# DB_Capacitance-X02.net
KiCad netlist of a schematic drawn in Altium Designer
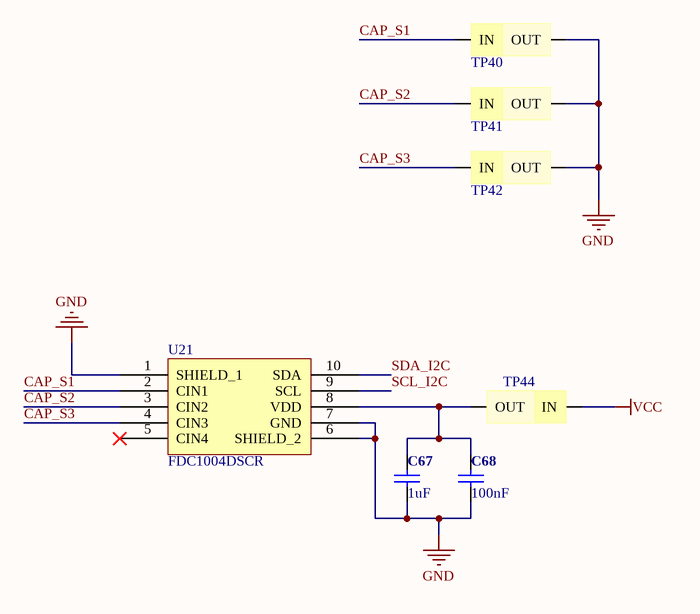
[diagram p0: DB_Capacitance-X02.SchDoc]

(export (version "E")
  (design (tool "Eeschema 10.0.6"))
  (components
    (comp (ref "C67")
      (value "1uF")
      (footprint "C0402")
      (fields
        (field (name "MANUFACTURER") "Yageo")
        (field (name "MANUFACTURER PART NUMBER") "CC0402MRX5R5BB105")
        (field (name "TOLERANCE") "20%")
      )
      (libsource (lib "DB-X02") (part "C-0402(1005)"))
    )
    (comp (ref "C68")
      (value "100nF")
      (footprint "C0402")
      (fields
        (field (name "MANUFACTURER") "Taiyo Yuden")
        (field (name "MANUFACTURER PART NUMBER") "TMK105BJ104KV-F")
        (field (name "TOLERANCE") "10%")
      )
      (libsource (lib "DB-X02") (part "C-0402(1005)"))
    )
    (comp (ref "TP40")
      (value "JUMPER")
      (footprint "JUMPER")
      (description "SHUNT LP W/HANDLE 2 POS 30AU")
      (fields
        (field (name "MANUFACTURER") "TE Connectivity")
        (field (name "MANUFACTURER PART NUMBER") "8815452")
      )
      (libsource (lib "") (part "JUMPER_1"))
    )
    (comp (ref "TP41")
      (value "JUMPER")
      (footprint "JUMPER")
      (description "SHUNT LP W/HANDLE 2 POS 30AU")
      (fields
        (field (name "MANUFACTURER") "TE Connectivity")
        (field (name "MANUFACTURER PART NUMBER") "8815452")
      )
      (libsource (lib "") (part "JUMPER_1"))
    )
    (comp (ref "TP42")
      (value "JUMPER")
      (footprint "JUMPER")
      (description "SHUNT LP W/HANDLE 2 POS 30AU")
      (fields
        (field (name "MANUFACTURER") "TE Connectivity")
        (field (name "MANUFACTURER PART NUMBER") "8815452")
      )
      (libsource (lib "") (part "JUMPER_1"))
    )
    (comp (ref "TP44")
      (value "JUMPER")
      (footprint "JUMPER")
      (description "SHUNT LP W/HANDLE 2 POS 30AU")
      (fields
        (field (name "MANUFACTURER") "TE Connectivity")
        (field (name "MANUFACTURER PART NUMBER") "8815452")
      )
      (libsource (lib "DB-X02") (part "JUMPER"))
    )
    (comp (ref "U21")
      (value "4 CHANNEL CDC")
      (footprint "WSON-10 3X3MM")
      (description "Analog Circuit, 1 Func, 4 Channel, PDSO10")
      (fields
        (field (name "MANUFACTURER") "Texas Instruments")
        (field (name "MANUFACTURER PART NUMBER") "FDC1004DSCR")
      )
      (libsource (lib "DB-X02") (part "FDC1004"))
    )
  )
  (nets
    (net (code "1") (name "/CAP_S1") (class "Default")
      (node (ref "TP40") (pin "1") (pinfunction "IN_1") (pintype "passive"))
      (node (ref "U21") (pin "2") (pinfunction "CIN1_2") (pintype "passive"))
    )
    (net (code "2") (name "/CAP_S2") (class "Default")
      (node (ref "TP41") (pin "1") (pinfunction "IN_1") (pintype "passive"))
      (node (ref "U21") (pin "3") (pinfunction "CIN2_3") (pintype "passive"))
    )
    (net (code "3") (name "/CAP_S3") (class "Default")
      (node (ref "TP42") (pin "1") (pinfunction "IN_1") (pintype "passive"))
      (node (ref "U21") (pin "4") (pinfunction "CIN3_4") (pintype "passive"))
    )
    (net (code "4") (name "/SCL_I2C") (class "Default")
      (node (ref "U21") (pin "9") (pinfunction "SCL_9") (pintype "passive"))
    )
    (net (code "5") (name "/SDA_I2C") (class "Default")
      (node (ref "U21") (pin "10") (pinfunction "SDA_10") (pintype "passive"))
    )
    (net (code "6") (name "GND") (class "Default")
      (node (ref "C67") (pin "2") (pinfunction "2_2") (pintype "passive"))
      (node (ref "C68") (pin "2") (pinfunction "2_2") (pintype "passive"))
      (node (ref "TP40") (pin "2") (pinfunction "OUT_2") (pintype "passive"))
      (node (ref "TP41") (pin "2") (pinfunction "OUT_2") (pintype "passive"))
      (node (ref "TP42") (pin "2") (pinfunction "OUT_2") (pintype "passive"))
      (node (ref "U21") (pin "1") (pinfunction "SHIELD_1_1") (pintype "passive"))
      (node (ref "U21") (pin "6") (pinfunction "SHIELD_2_6") (pintype "passive"))
      (node (ref "U21") (pin "7") (pinfunction "GND_7") (pintype "passive"))
    )
    (net (code "7") (name "Net-(TP44-OUT)") (class "Default")
      (node (ref "C67") (pin "1") (pinfunction "1_1") (pintype "passive"))
      (node (ref "C68") (pin "1") (pinfunction "1_1") (pintype "passive"))
      (node (ref "TP44") (pin "2") (pinfunction "OUT_2") (pintype "passive"))
      (node (ref "U21") (pin "8") (pinfunction "VDD_8") (pintype "passive"))
    )
    (net (code "8") (name "VCC") (class "Default")
      (node (ref "TP44") (pin "1") (pinfunction "IN_1") (pintype "passive"))
    )
    (net (code "9") (name "unconnected-(U21-CIN4-Pad5)") (class "Default")
      (node (ref "U21") (pin "5") (pinfunction "CIN4_5") (pintype "passive+no_connect"))
    )
  )
)
